# Pure_Noise.net
KiCad netlist of a schematic drawn in EAGLE
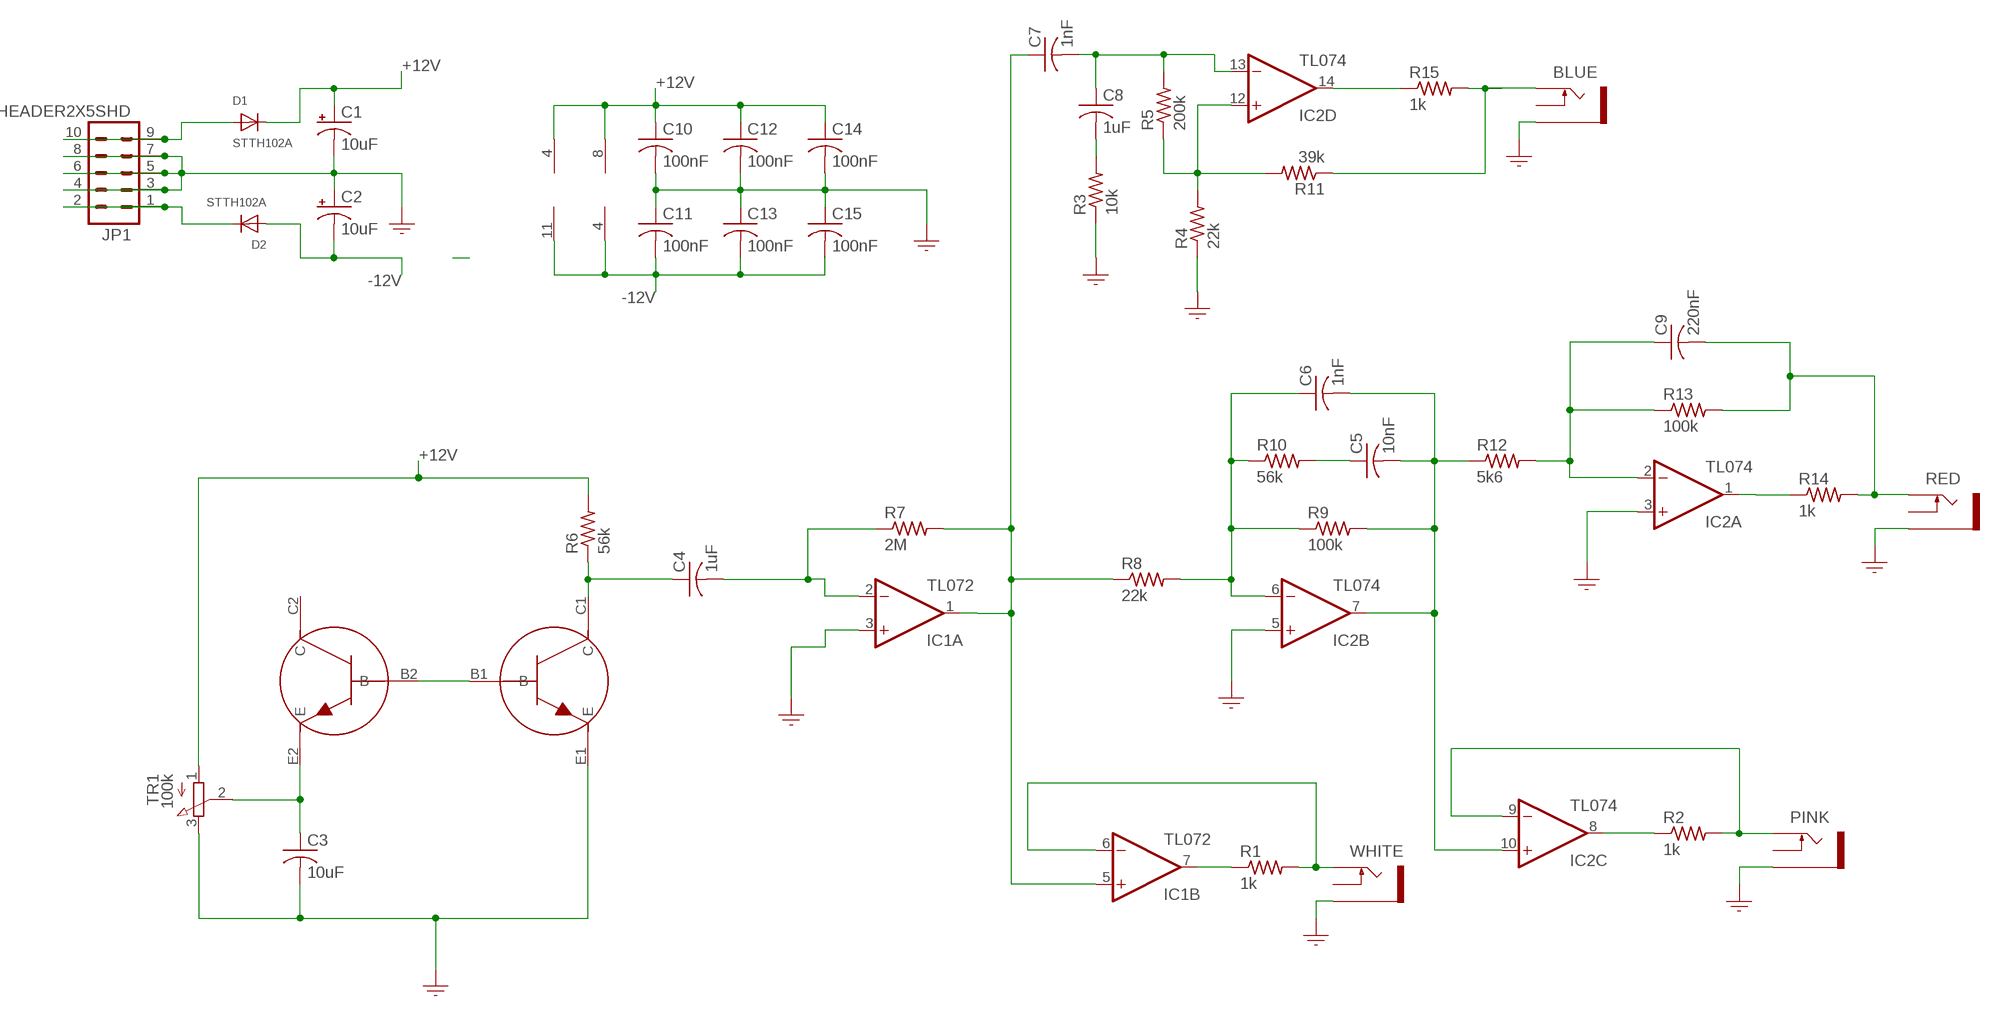
[diagram p0: schematic, sheet 1]

(export (version "E")
  (design (tool "Eeschema 10.0.6"))
  (components
    (comp (ref "BLUE")
      (value "SOCKET_MONO_3.5MMPJ301M-12")
      (footprint "eagle-import:PJ301M-12")
      (libsource (lib "eagle-import") (part "SOCKET_MONO_3.5MMPJ301M-12"))
    )
    (comp (ref "C1")
      (value "10uF")
      (footprint "eagle-import:153CLV-0505")
      (libsource (lib "eagle-import") (part "CAPACITOR_POL-US153CLV-0505"))
    )
    (comp (ref "C2")
      (value "10uF")
      (footprint "eagle-import:153CLV-0505")
      (libsource (lib "eagle-import") (part "CAPACITOR_POL-US153CLV-0505"))
    )
    (comp (ref "C3")
      (value "10uF")
      (footprint "eagle-import:C0805")
      (libsource (lib "eagle-import") (part "CAPACITOR-USC0805"))
    )
    (comp (ref "C4")
      (value "1uF")
      (footprint "eagle-import:C0805")
      (libsource (lib "eagle-import") (part "CAPACITOR-USC0805"))
    )
    (comp (ref "C5")
      (value "10nF")
      (footprint "eagle-import:C0805")
      (libsource (lib "eagle-import") (part "CAPACITOR-USC0805"))
    )
    (comp (ref "C6")
      (value "1nF")
      (footprint "eagle-import:C0805")
      (libsource (lib "eagle-import") (part "CAPACITOR-USC0805"))
    )
    (comp (ref "C7")
      (value "1nF")
      (footprint "eagle-import:C0805")
      (libsource (lib "eagle-import") (part "CAPACITOR-USC0805"))
    )
    (comp (ref "C8")
      (value "1uF")
      (footprint "eagle-import:C0805")
      (libsource (lib "eagle-import") (part "CAPACITOR-USC0805"))
    )
    (comp (ref "C9")
      (value "220nF")
      (footprint "eagle-import:C0805")
      (libsource (lib "eagle-import") (part "CAPACITOR-USC0805"))
    )
    (comp (ref "C10")
      (value "100nF")
      (footprint "eagle-import:C0805")
      (libsource (lib "eagle-import") (part "CAPACITOR-USC0805"))
    )
    (comp (ref "C11")
      (value "100nF")
      (footprint "eagle-import:C0805")
      (libsource (lib "eagle-import") (part "CAPACITOR-USC0805"))
    )
    (comp (ref "C12")
      (value "100nF")
      (footprint "eagle-import:C0805")
      (libsource (lib "eagle-import") (part "CAPACITOR-USC0805"))
    )
    (comp (ref "C13")
      (value "100nF")
      (footprint "eagle-import:C0805")
      (libsource (lib "eagle-import") (part "CAPACITOR-USC0805"))
    )
    (comp (ref "C14")
      (value "100nF")
      (footprint "eagle-import:C0805")
      (libsource (lib "eagle-import") (part "CAPACITOR-USC0805"))
    )
    (comp (ref "C15")
      (value "100nF")
      (footprint "eagle-import:C0805")
      (libsource (lib "eagle-import") (part "CAPACITOR-USC0805"))
    )
    (comp (ref "D1")
      (value "STTH102A")
      (footprint "eagle-import:SMADIODE")
      (libsource (lib "eagle-import") (part "DIODESMA"))
    )
    (comp (ref "D2")
      (value "STTH102A")
      (footprint "eagle-import:SMADIODE")
      (libsource (lib "eagle-import") (part "DIODESMA"))
    )
    (comp (ref "IC1")
      (value "TL072")
      (footprint "eagle-import:SO08")
      (libsource (lib "eagle-import") (part "OPAMP_DUALD"))
    )
    (comp (ref "IC2")
      (value "TL074")
      (footprint "eagle-import:SO14")
      (libsource (lib "eagle-import") (part "OPAMP_QUADD"))
    )
    (comp (ref "JP1")
      (value "HEADER2X5SHD")
      (footprint "eagle-import:2X5-SHROUDED")
      (libsource (lib "eagle-import") (part "HEADER2X5SHD"))
    )
    (comp (ref "PINK")
      (value "SOCKET_MONO_3.5MMPJ301M-12")
      (footprint "eagle-import:PJ301M-12")
      (libsource (lib "eagle-import") (part "SOCKET_MONO_3.5MMPJ301M-12"))
    )
    (comp (ref "R1")
      (value "1k")
      (footprint "eagle-import:R0805")
      (libsource (lib "eagle-import") (part "RESISTOR_USR0805"))
    )
    (comp (ref "R2")
      (value "1k")
      (footprint "eagle-import:R0805")
      (libsource (lib "eagle-import") (part "RESISTOR_USR0805"))
    )
    (comp (ref "R3")
      (value "10k")
      (footprint "eagle-import:R0805")
      (libsource (lib "eagle-import") (part "RESISTOR_USR0805"))
    )
    (comp (ref "R4")
      (value "22k")
      (footprint "eagle-import:R0805")
      (libsource (lib "eagle-import") (part "RESISTOR_USR0805"))
    )
    (comp (ref "R5")
      (value "200k")
      (footprint "eagle-import:R0805")
      (libsource (lib "eagle-import") (part "RESISTOR_USR0805"))
    )
    (comp (ref "R6")
      (value "56k")
      (footprint "eagle-import:R0805")
      (libsource (lib "eagle-import") (part "RESISTOR_USR0805"))
    )
    (comp (ref "R7")
      (value "2M")
      (footprint "eagle-import:R0805")
      (libsource (lib "eagle-import") (part "RESISTOR_USR0805"))
    )
    (comp (ref "R8")
      (value "22k")
      (footprint "eagle-import:R0805")
      (libsource (lib "eagle-import") (part "RESISTOR_USR0805"))
    )
    (comp (ref "R9")
      (value "100k")
      (footprint "eagle-import:R0805")
      (libsource (lib "eagle-import") (part "RESISTOR_USR0805"))
    )
    (comp (ref "R10")
      (value "56k")
      (footprint "eagle-import:R0805")
      (libsource (lib "eagle-import") (part "RESISTOR_USR0805"))
    )
    (comp (ref "R11")
      (value "39k")
      (footprint "eagle-import:R0805")
      (libsource (lib "eagle-import") (part "RESISTOR_USR0805"))
    )
    (comp (ref "R12")
      (value "5k6")
      (footprint "eagle-import:R0805")
      (libsource (lib "eagle-import") (part "RESISTOR_USR0805"))
    )
    (comp (ref "R13")
      (value "100k")
      (footprint "eagle-import:R0805")
      (libsource (lib "eagle-import") (part "RESISTOR_USR0805"))
    )
    (comp (ref "R14")
      (value "1k")
      (footprint "eagle-import:R0805")
      (libsource (lib "eagle-import") (part "RESISTOR_USR0805"))
    )
    (comp (ref "R15")
      (value "1k")
      (footprint "eagle-import:R0805")
      (libsource (lib "eagle-import") (part "RESISTOR_USR0805"))
    )
    (comp (ref "RED")
      (value "SOCKET_MONO_3.5MMPJ301M-12")
      (footprint "eagle-import:PJ301M-12")
      (libsource (lib "eagle-import") (part "SOCKET_MONO_3.5MMPJ301M-12"))
    )
    (comp (ref "T1")
      (value "DMMT3904W-7-F")
      (footprint "eagle-import:TRANS_PAIR")
      (libsource (lib "eagle-import") (part "TRANSISTOR_PAIR_NPN"))
    )
    (comp (ref "TR1")
      (value "100k")
      (footprint "eagle-import:TRIMMER_TH")
      (libsource (lib "eagle-import") (part "RESISTOR_VARIABLETRIMMER_TH"))
    )
    (comp (ref "WHITE")
      (value "SOCKET_MONO_3.5MMPJ301M-12")
      (footprint "eagle-import:PJ301M-12")
      (libsource (lib "eagle-import") (part "SOCKET_MONO_3.5MMPJ301M-12"))
    )
  )
  (nets
    (net (code "1") (name "/+12V") (class "Default")
      (node (ref "C1") (pin "+") (pinfunction "+_+") (pintype "passive"))
      (node (ref "C10") (pin "1") (pinfunction "1_1") (pintype "passive"))
      (node (ref "C12") (pin "1") (pinfunction "1_1") (pintype "passive"))
      (node (ref "C14") (pin "1") (pinfunction "1_1") (pintype "passive"))
      (node (ref "D1") (pin "C") (pinfunction "C_C") (pintype "passive"))
      (node (ref "IC1") (pin "8") (pinfunction "V+_8") (pintype "power_in"))
      (node (ref "IC2") (pin "4") (pinfunction "V+_4") (pintype "power_in"))
      (node (ref "R6") (pin "2") (pinfunction "2_2") (pintype "passive"))
      (node (ref "TR1") (pin "1") (pinfunction "1_1") (pintype "passive"))
    )
    (net (code "2") (name "/-12V") (class "Default")
      (node (ref "C11") (pin "2") (pinfunction "2_2") (pintype "passive"))
      (node (ref "C13") (pin "2") (pinfunction "2_2") (pintype "passive"))
      (node (ref "C15") (pin "2") (pinfunction "2_2") (pintype "passive"))
      (node (ref "C2") (pin "-") (pinfunction "-_-") (pintype "passive"))
      (node (ref "D2") (pin "A") (pinfunction "A_A") (pintype "passive"))
      (node (ref "IC1") (pin "4") (pinfunction "V-_4") (pintype "power_in"))
      (node (ref "IC2") (pin "11") (pinfunction "V-_11") (pintype "power_in"))
    )
    (net (code "3") (name "GND") (class "Default")
      (node (ref "BLUE") (pin "GND") (pinfunction "SLEEVE_GND") (pintype "passive"))
      (node (ref "C1") (pin "-") (pinfunction "-_-") (pintype "passive"))
      (node (ref "C10") (pin "2") (pinfunction "2_2") (pintype "passive"))
      (node (ref "C11") (pin "1") (pinfunction "1_1") (pintype "passive"))
      (node (ref "C12") (pin "2") (pinfunction "2_2") (pintype "passive"))
      (node (ref "C13") (pin "1") (pinfunction "1_1") (pintype "passive"))
      (node (ref "C14") (pin "2") (pinfunction "2_2") (pintype "passive"))
      (node (ref "C15") (pin "1") (pinfunction "1_1") (pintype "passive"))
      (node (ref "C2") (pin "+") (pinfunction "+_+") (pintype "passive"))
      (node (ref "C3") (pin "2") (pinfunction "2_2") (pintype "passive"))
      (node (ref "IC1") (pin "3") (pinfunction "+IN_3") (pintype "input"))
      (node (ref "IC2") (pin "3") (pinfunction "+IN_3") (pintype "input"))
      (node (ref "IC2") (pin "5") (pinfunction "+IN_5") (pintype "input"))
      (node (ref "JP1") (pin "3") (pinfunction "3_3") (pintype "passive"))
      (node (ref "JP1") (pin "4") (pinfunction "4_4") (pintype "passive"))
      (node (ref "JP1") (pin "5") (pinfunction "5_5") (pintype "passive"))
      (node (ref "JP1") (pin "6") (pinfunction "6_6") (pintype "passive"))
      (node (ref "JP1") (pin "7") (pinfunction "7_7") (pintype "passive"))
      (node (ref "JP1") (pin "8") (pinfunction "8_8") (pintype "passive"))
      (node (ref "PINK") (pin "GND") (pinfunction "SLEEVE_GND") (pintype "passive"))
      (node (ref "R3") (pin "1") (pinfunction "1_1") (pintype "passive"))
      (node (ref "R4") (pin "1") (pinfunction "1_1") (pintype "passive"))
      (node (ref "RED") (pin "GND") (pinfunction "SLEEVE_GND") (pintype "passive"))
      (node (ref "T1") (pin "E1") (pinfunction "E_E1") (pintype "bidirectional"))
      (node (ref "TR1") (pin "3") (pinfunction "3_3") (pintype "passive"))
      (node (ref "WHITE") (pin "GND") (pinfunction "SLEEVE_GND") (pintype "passive"))
    )
    (net (code "4") (name "Net-(BLUE-PadTIP)") (class "Default")
      (node (ref "BLUE") (pin "TIP") (pinfunction "TIP_TIP") (pintype "passive"))
      (node (ref "R11") (pin "1") (pinfunction "1_1") (pintype "passive"))
      (node (ref "R15") (pin "2") (pinfunction "2_2") (pintype "passive"))
    )
    (net (code "5") (name "Net-(C5-Pad1)") (class "Default")
      (node (ref "C5") (pin "1") (pinfunction "1_1") (pintype "passive"))
      (node (ref "R10") (pin "2") (pinfunction "2_2") (pintype "passive"))
    )
    (net (code "6") (name "Net-(C8-Pad2)") (class "Default")
      (node (ref "C8") (pin "2") (pinfunction "2_2") (pintype "passive"))
      (node (ref "R3") (pin "2") (pinfunction "2_2") (pintype "passive"))
    )
    (net (code "7") (name "Net-(C9-Pad2)") (class "Default")
      (node (ref "C9") (pin "2") (pinfunction "2_2") (pintype "passive"))
      (node (ref "R13") (pin "2") (pinfunction "2_2") (pintype "passive"))
      (node (ref "R14") (pin "2") (pinfunction "2_2") (pintype "passive"))
      (node (ref "RED") (pin "TIP") (pinfunction "TIP_TIP") (pintype "passive"))
    )
    (net (code "8") (name "Net-(D1-PadA)") (class "Default")
      (node (ref "D1") (pin "A") (pinfunction "A_A") (pintype "passive"))
      (node (ref "JP1") (pin "10") (pinfunction "10_10") (pintype "passive"))
      (node (ref "JP1") (pin "9") (pinfunction "9_9") (pintype "passive"))
    )
    (net (code "9") (name "Net-(D2-PadC)") (class "Default")
      (node (ref "D2") (pin "C") (pinfunction "C_C") (pintype "passive"))
      (node (ref "JP1") (pin "1") (pinfunction "1_1") (pintype "passive"))
      (node (ref "JP1") (pin "2") (pinfunction "2_2") (pintype "passive"))
    )
    (net (code "10") (name "Net-(IC1A--IN)") (class "Default")
      (node (ref "C4") (pin "2") (pinfunction "2_2") (pintype "passive"))
      (node (ref "IC1") (pin "2") (pinfunction "-IN_2") (pintype "input"))
      (node (ref "R7") (pin "1") (pinfunction "1_1") (pintype "passive"))
    )
    (net (code "11") (name "Net-(IC1A-OUT)") (class "Default")
      (node (ref "C7") (pin "1") (pinfunction "1_1") (pintype "passive"))
      (node (ref "IC1") (pin "1") (pinfunction "OUT_1") (pintype "output"))
      (node (ref "IC1") (pin "5") (pinfunction "+IN_5") (pintype "input"))
      (node (ref "R7") (pin "2") (pinfunction "2_2") (pintype "passive"))
      (node (ref "R8") (pin "1") (pinfunction "1_1") (pintype "passive"))
    )
    (net (code "12") (name "Net-(IC1B--IN)") (class "Default")
      (node (ref "IC1") (pin "6") (pinfunction "-IN_6") (pintype "input"))
      (node (ref "R1") (pin "2") (pinfunction "2_2") (pintype "passive"))
      (node (ref "WHITE") (pin "TIP") (pinfunction "TIP_TIP") (pintype "passive"))
    )
    (net (code "13") (name "Net-(IC1B-OUT)") (class "Default")
      (node (ref "IC1") (pin "7") (pinfunction "OUT_7") (pintype "output"))
      (node (ref "R1") (pin "1") (pinfunction "1_1") (pintype "passive"))
    )
    (net (code "14") (name "Net-(IC2A--IN)") (class "Default")
      (node (ref "C9") (pin "1") (pinfunction "1_1") (pintype "passive"))
      (node (ref "IC2") (pin "2") (pinfunction "-IN_2") (pintype "input"))
      (node (ref "R12") (pin "2") (pinfunction "2_2") (pintype "passive"))
      (node (ref "R13") (pin "1") (pinfunction "1_1") (pintype "passive"))
    )
    (net (code "15") (name "Net-(IC2A-OUT)") (class "Default")
      (node (ref "IC2") (pin "1") (pinfunction "OUT_1") (pintype "output"))
      (node (ref "R14") (pin "1") (pinfunction "1_1") (pintype "passive"))
    )
    (net (code "16") (name "Net-(IC2B--IN)") (class "Default")
      (node (ref "C6") (pin "1") (pinfunction "1_1") (pintype "passive"))
      (node (ref "IC2") (pin "6") (pinfunction "-IN_6") (pintype "input"))
      (node (ref "R10") (pin "1") (pinfunction "1_1") (pintype "passive"))
      (node (ref "R8") (pin "2") (pinfunction "2_2") (pintype "passive"))
      (node (ref "R9") (pin "1") (pinfunction "1_1") (pintype "passive"))
    )
    (net (code "17") (name "Net-(IC2B-OUT)") (class "Default")
      (node (ref "C5") (pin "2") (pinfunction "2_2") (pintype "passive"))
      (node (ref "C6") (pin "2") (pinfunction "2_2") (pintype "passive"))
      (node (ref "IC2") (pin "10") (pinfunction "+IN_10") (pintype "input"))
      (node (ref "IC2") (pin "7") (pinfunction "OUT_7") (pintype "output"))
      (node (ref "R12") (pin "1") (pinfunction "1_1") (pintype "passive"))
      (node (ref "R9") (pin "2") (pinfunction "2_2") (pintype "passive"))
    )
    (net (code "18") (name "Net-(IC2C--IN)") (class "Default")
      (node (ref "IC2") (pin "9") (pinfunction "-IN_9") (pintype "input"))
      (node (ref "PINK") (pin "TIP") (pinfunction "TIP_TIP") (pintype "passive"))
      (node (ref "R2") (pin "2") (pinfunction "2_2") (pintype "passive"))
    )
    (net (code "19") (name "Net-(IC2C-OUT)") (class "Default")
      (node (ref "IC2") (pin "8") (pinfunction "OUT_8") (pintype "output"))
      (node (ref "R2") (pin "1") (pinfunction "1_1") (pintype "passive"))
    )
    (net (code "20") (name "Net-(IC2D-+IN)") (class "Default")
      (node (ref "IC2") (pin "12") (pinfunction "+IN_12") (pintype "input"))
      (node (ref "R11") (pin "2") (pinfunction "2_2") (pintype "passive"))
      (node (ref "R4") (pin "2") (pinfunction "2_2") (pintype "passive"))
      (node (ref "R5") (pin "1") (pinfunction "1_1") (pintype "passive"))
    )
    (net (code "21") (name "Net-(IC2D--IN)") (class "Default")
      (node (ref "C7") (pin "2") (pinfunction "2_2") (pintype "passive"))
      (node (ref "C8") (pin "1") (pinfunction "1_1") (pintype "passive"))
      (node (ref "IC2") (pin "13") (pinfunction "-IN_13") (pintype "input"))
      (node (ref "R5") (pin "2") (pinfunction "2_2") (pintype "passive"))
    )
    (net (code "22") (name "Net-(IC2D-OUT)") (class "Default")
      (node (ref "IC2") (pin "14") (pinfunction "OUT_14") (pintype "output"))
      (node (ref "R15") (pin "1") (pinfunction "1_1") (pintype "passive"))
    )
    (net (code "23") (name "Net-(T1A-B)") (class "Default")
      (node (ref "T1") (pin "B1") (pinfunction "B_B1") (pintype "bidirectional"))
      (node (ref "T1") (pin "B2") (pinfunction "B_B2") (pintype "bidirectional"))
    )
    (net (code "24") (name "Net-(T1A-C)") (class "Default")
      (node (ref "C4") (pin "1") (pinfunction "1_1") (pintype "passive"))
      (node (ref "R6") (pin "1") (pinfunction "1_1") (pintype "passive"))
      (node (ref "T1") (pin "C1") (pinfunction "C_C1") (pintype "bidirectional"))
    )
    (net (code "25") (name "Net-(T1B-E)") (class "Default")
      (node (ref "C3") (pin "1") (pinfunction "1_1") (pintype "passive"))
      (node (ref "T1") (pin "E2") (pinfunction "E_E2") (pintype "bidirectional"))
      (node (ref "TR1") (pin "2") (pinfunction "2_2") (pintype "passive"))
    )
    (net (code "26") (name "unconnected-(BLUE-SWITCH-PadNORM)") (class "Default")
      (node (ref "BLUE") (pin "NORM") (pinfunction "SWITCH_NORM") (pintype "passive"))
    )
    (net (code "27") (name "unconnected-(PINK-SWITCH-PadNORM)") (class "Default")
      (node (ref "PINK") (pin "NORM") (pinfunction "SWITCH_NORM") (pintype "passive"))
    )
    (net (code "28") (name "unconnected-(RED-SWITCH-PadNORM)") (class "Default")
      (node (ref "RED") (pin "NORM") (pinfunction "SWITCH_NORM") (pintype "passive"))
    )
    (net (code "29") (name "unconnected-(T1B-C-PadC2)") (class "Default")
      (node (ref "T1") (pin "C2") (pinfunction "C_C2") (pintype "bidirectional"))
    )
    (net (code "30") (name "unconnected-(WHITE-SWITCH-PadNORM)") (class "Default")
      (node (ref "WHITE") (pin "NORM") (pinfunction "SWITCH_NORM") (pintype "passive"))
    )
  )
)
